# power_supply.net
KiCad netlist of a schematic drawn in Altium Designer
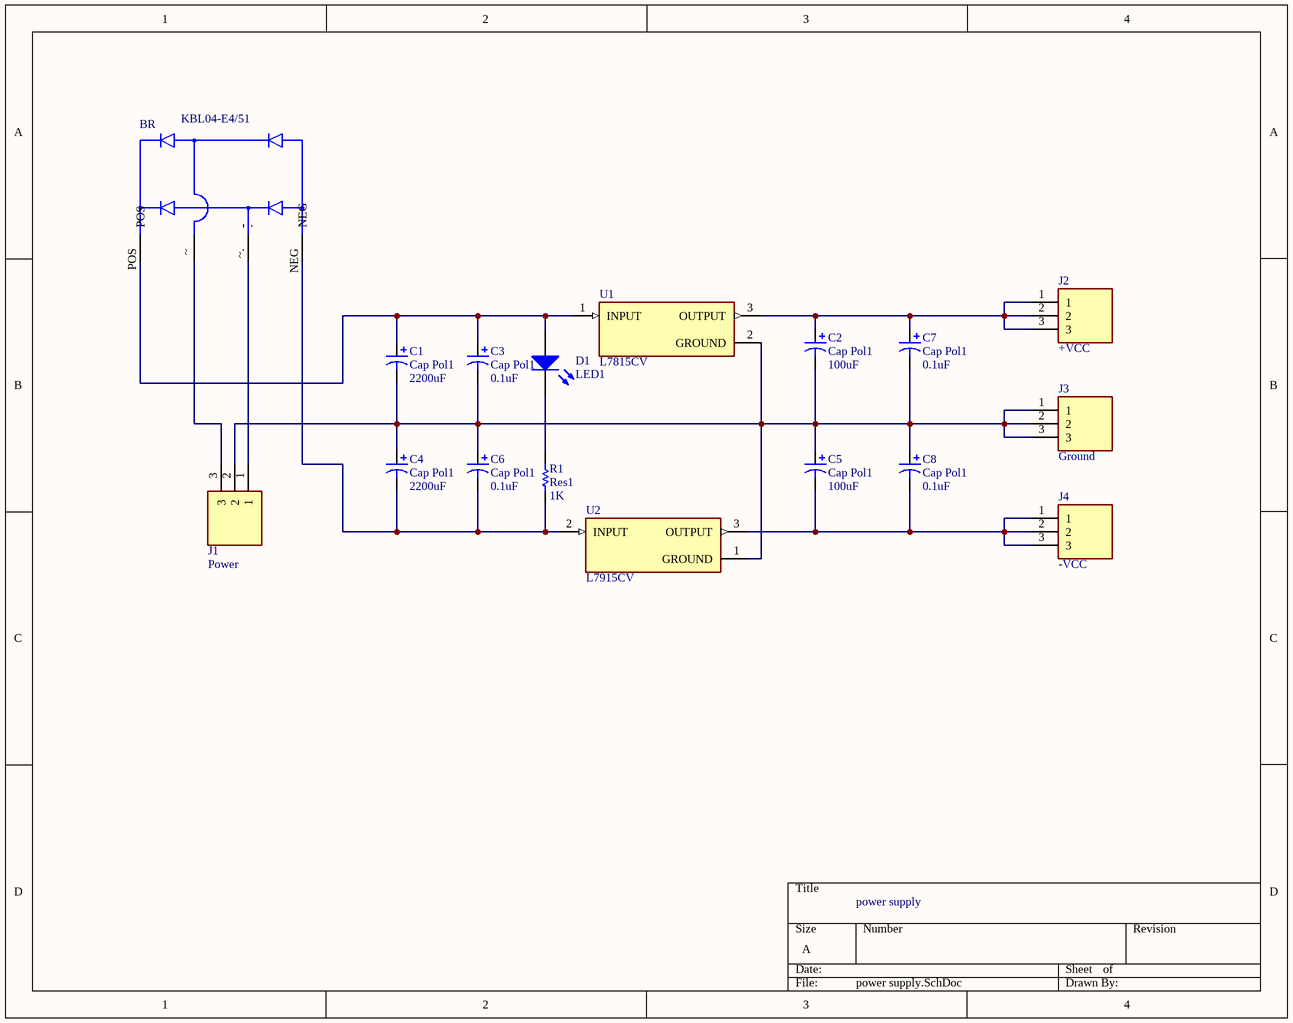
[diagram p0: power supply.SchDoc]

(export (version "E")
  (design (tool "Eeschema 10.0.6"))
  (components
    (comp (ref "BR")
      (value "KBL04-E4/51")
      (footprint "DIOB_KBL04-E4/51")
      (description "Bridge Rectifier Single Phase Standard 400V Through Hole KBL")
      (fields (field (name "MF") "Vishay"))
      (libsource (lib "KBL04-E4_51") (part "KBL04-E4/51"))
    )
    (comp (ref "C1")
      (value "Cap Pol1")
      (footprint "RB7.6-15")
      (description "Polarized Capacitor (Radial)")
      (fields (field (name "ALTIUM_VALUE") "2200uF") (field (name "PUBLISHER") "Altium Limited"))
      (libsource (lib "Miscellaneous Devices") (part "Cap Pol1"))
    )
    (comp (ref "C2")
      (value "Cap Pol1")
      (footprint "RB7.6-15")
      (description "Polarized Capacitor (Radial)")
      (fields (field (name "ALTIUM_VALUE") "100uF") (field (name "PUBLISHER") "Altium Limited"))
      (libsource (lib "Miscellaneous Devices") (part "Cap Pol1"))
    )
    (comp (ref "C3")
      (value "Cap Pol1")
      (footprint "RB7.6-15")
      (description "Polarized Capacitor (Radial)")
      (fields (field (name "ALTIUM_VALUE") "0.1uF") (field (name "PUBLISHER") "Altium Limited"))
      (libsource (lib "Miscellaneous Devices") (part "Cap Pol1"))
    )
    (comp (ref "C4")
      (value "Cap Pol1")
      (footprint "RB7.6-15")
      (description "Polarized Capacitor (Radial)")
      (fields (field (name "ALTIUM_VALUE") "2200uF") (field (name "PUBLISHER") "Altium Limited"))
      (libsource (lib "Miscellaneous Devices") (part "Cap Pol1"))
    )
    (comp (ref "C5")
      (value "Cap Pol1")
      (footprint "RB7.6-15")
      (description "Polarized Capacitor (Radial)")
      (fields (field (name "ALTIUM_VALUE") "100uF") (field (name "PUBLISHER") "Altium Limited"))
      (libsource (lib "Miscellaneous Devices") (part "Cap Pol1"))
    )
    (comp (ref "C6")
      (value "Cap Pol1")
      (footprint "RB7.6-15")
      (description "Polarized Capacitor (Radial)")
      (fields (field (name "ALTIUM_VALUE") "0.1uF") (field (name "PUBLISHER") "Altium Limited"))
      (libsource (lib "Miscellaneous Devices") (part "Cap Pol1"))
    )
    (comp (ref "C7")
      (value "Cap Pol1")
      (footprint "RB7.6-15")
      (description "Polarized Capacitor (Radial)")
      (fields (field (name "ALTIUM_VALUE") "0.1uF") (field (name "PUBLISHER") "Altium Limited"))
      (libsource (lib "Miscellaneous Devices") (part "Cap Pol1"))
    )
    (comp (ref "C8")
      (value "Cap Pol1")
      (footprint "RB7.6-15")
      (description "Polarized Capacitor (Radial)")
      (fields (field (name "ALTIUM_VALUE") "0.1uF") (field (name "PUBLISHER") "Altium Limited"))
      (libsource (lib "Miscellaneous Devices") (part "Cap Pol1"))
    )
    (comp (ref "D1")
      (value "LED1")
      (footprint "LED-1")
      (description "Typical RED GaAs LED")
      (fields (field (name "PUBLISHER") "Altium Limited"))
      (libsource (lib "Miscellaneous Devices") (part "LED1"))
    )
    (comp (ref "J1")
      (value "Power")
      (footprint "CUI_TB005-762-03BE")
      (description "2~24 Poles, Screw Type, Horizontal, 7.62 Pitch, 26~10 _AWG_, Terminal Block Connector")
      (fields (field (name "MP") "TB005-762-03BE") (field (name "MF") "CUI Devices"))
      (libsource (lib "") (part "TB005-762-03BE_1"))
    )
    (comp (ref "J2")
      (value "+VCC")
      (footprint "CUI_TB005-762-03BE")
      (description "2~24 Poles, Screw Type, Horizontal, 7.62 Pitch, 26~10 _AWG_, Terminal Block Connector")
      (fields (field (name "MP") "TB005-762-03BE") (field (name "MF") "CUI Devices"))
      (libsource (lib "TB005-762-03BE") (part "TB005-762-03BE"))
    )
    (comp (ref "J3")
      (value "Ground")
      (footprint "CUI_TB005-762-03BE")
      (description "2~24 Poles, Screw Type, Horizontal, 7.62 Pitch, 26~10 _AWG_, Terminal Block Connector")
      (fields (field (name "MP") "TB005-762-03BE") (field (name "MF") "CUI Devices"))
      (libsource (lib "TB005-762-03BE") (part "TB005-762-03BE"))
    )
    (comp (ref "J4")
      (value "-VCC")
      (footprint "CUI_TB005-762-03BE")
      (description "2~24 Poles, Screw Type, Horizontal, 7.62 Pitch, 26~10 _AWG_, Terminal Block Connector")
      (fields (field (name "MP") "TB005-762-03BE") (field (name "MF") "CUI Devices"))
      (libsource (lib "TB005-762-03BE") (part "TB005-762-03BE"))
    )
    (comp (ref "R1")
      (value "Res1")
      (footprint "AXIAL-0.3")
      (description "Resistor")
      (fields (field (name "ALTIUM_VALUE") "1K") (field (name "PUBLISHER") "Altium Limited"))
      (libsource (lib "Miscellaneous Devices") (part "Res1"))
    )
    (comp (ref "U1")
      (value "L7815CV")
      (footprint "TO255P1040X460X1935-3")
      (description "Linear Voltage Regulator IC 1 Output 1.5A TO-220AB")
      (fields (field (name "MF") "STMicroelectronics"))
      (libsource (lib "L7815CV") (part "L7815CV"))
    )
    (comp (ref "U2")
      (value "L7915CV")
      (footprint "TO255P1040X460X1935-3")
      (description "Linear Voltage Regulator IC 1 Output 1.5A TO-220AB")
      (fields (field (name "MF") "STMicroelectronics"))
      (libsource (lib "L7915CV") (part "L7915CV"))
    )
  )
  (nets
    (net (code "1") (name "Net-(BR-Pad~)") (class "Default")
      (node (ref "BR") (pin "~") (pintype "passive"))
      (node (ref "J1") (pin "3") (pinfunction "3_3") (pintype "passive"))
    )
    (net (code "2") (name "Net-(BR-~{.})") (class "Default")
      (node (ref "BR") (pin "~.") (pinfunction "~{.}_~.") (pintype "passive"))
      (node (ref "J1") (pin "1") (pinfunction "1_1") (pintype "passive"))
    )
    (net (code "3") (name "Net-(D1-A)") (class "Default")
      (node (ref "BR") (pin "POS") (pinfunction "POS_POS") (pintype "passive"))
      (node (ref "C1") (pin "1") (pinfunction "1_1") (pintype "passive"))
      (node (ref "C3") (pin "1") (pinfunction "1_1") (pintype "passive"))
      (node (ref "D1") (pin "1") (pinfunction "A_1") (pintype "passive"))
      (node (ref "U1") (pin "1") (pinfunction "INPUT_1") (pintype "input"))
    )
    (net (code "4") (name "Net-(D1-K)") (class "Default")
      (node (ref "D1") (pin "2") (pinfunction "K_2") (pintype "passive"))
      (node (ref "R1") (pin "2") (pinfunction "2_2") (pintype "passive"))
    )
    (net (code "5") (name "Net-(U1-GROUND)") (class "Default")
      (node (ref "C1") (pin "2") (pinfunction "2_2") (pintype "passive"))
      (node (ref "C2") (pin "2") (pinfunction "2_2") (pintype "passive"))
      (node (ref "C3") (pin "2") (pinfunction "2_2") (pintype "passive"))
      (node (ref "C4") (pin "1") (pinfunction "1_1") (pintype "passive"))
      (node (ref "C5") (pin "1") (pinfunction "1_1") (pintype "passive"))
      (node (ref "C6") (pin "1") (pinfunction "1_1") (pintype "passive"))
      (node (ref "C7") (pin "2") (pinfunction "2_2") (pintype "passive"))
      (node (ref "C8") (pin "1") (pinfunction "1_1") (pintype "passive"))
      (node (ref "J1") (pin "2") (pinfunction "2_2") (pintype "passive"))
      (node (ref "J3") (pin "1") (pinfunction "1_1") (pintype "passive"))
      (node (ref "J3") (pin "2") (pinfunction "2_2") (pintype "passive"))
      (node (ref "J3") (pin "3") (pinfunction "3_3") (pintype "passive"))
      (node (ref "U1") (pin "2") (pinfunction "GROUND_2") (pintype "power_in"))
      (node (ref "U2") (pin "1") (pinfunction "GROUND_1") (pintype "power_in"))
    )
    (net (code "6") (name "Net-(U1-OUTPUT)") (class "Default")
      (node (ref "C2") (pin "1") (pinfunction "1_1") (pintype "passive"))
      (node (ref "C7") (pin "1") (pinfunction "1_1") (pintype "passive"))
      (node (ref "J2") (pin "1") (pinfunction "1_1") (pintype "passive"))
      (node (ref "J2") (pin "2") (pinfunction "2_2") (pintype "passive"))
      (node (ref "J2") (pin "3") (pinfunction "3_3") (pintype "passive"))
      (node (ref "U1") (pin "3") (pinfunction "OUTPUT_3") (pintype "output"))
    )
    (net (code "7") (name "Net-(U2-INPUT)") (class "Default")
      (node (ref "BR") (pin "NEG") (pinfunction "NEG_NEG") (pintype "passive"))
      (node (ref "C4") (pin "2") (pinfunction "2_2") (pintype "passive"))
      (node (ref "C6") (pin "2") (pinfunction "2_2") (pintype "passive"))
      (node (ref "R1") (pin "1") (pinfunction "1_1") (pintype "passive"))
      (node (ref "U2") (pin "2") (pinfunction "INPUT_2") (pintype "input"))
    )
    (net (code "8") (name "Net-(U2-OUTPUT)") (class "Default")
      (node (ref "C5") (pin "2") (pinfunction "2_2") (pintype "passive"))
      (node (ref "C8") (pin "2") (pinfunction "2_2") (pintype "passive"))
      (node (ref "J4") (pin "1") (pinfunction "1_1") (pintype "passive"))
      (node (ref "J4") (pin "2") (pinfunction "2_2") (pintype "passive"))
      (node (ref "J4") (pin "3") (pinfunction "3_3") (pintype "passive"))
      (node (ref "U2") (pin "3") (pinfunction "OUTPUT_3") (pintype "output"))
    )
  )
)
